# Pogramador_FT230XQ.net
KiCad netlist of a schematic drawn in EAGLE
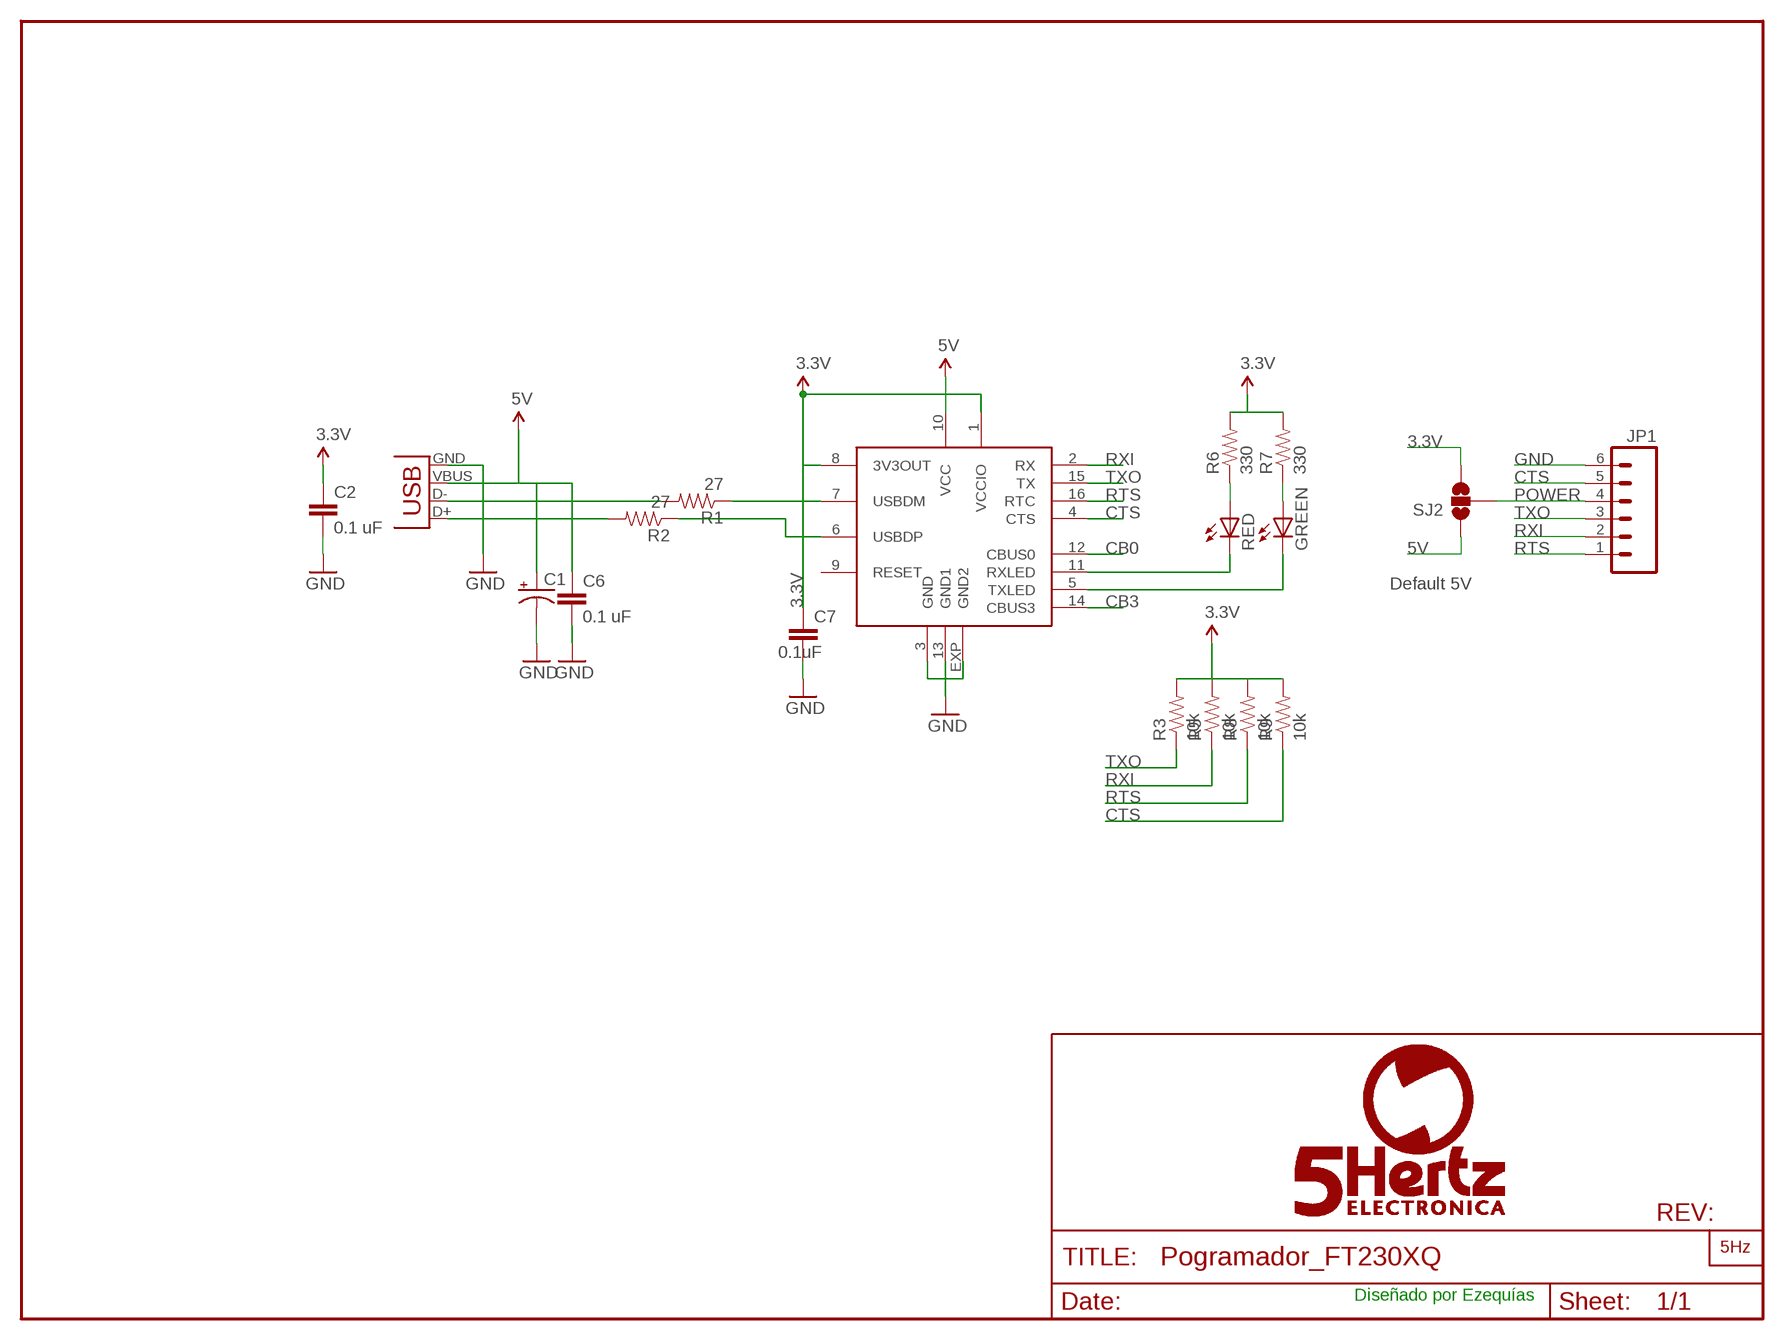
[diagram p0: schematic, sheet 1]

(export (version "E")
  (design (tool "Eeschema 10.0.6"))
  (components
    (comp (ref "C1")
      (value "CAP_POL1206")
      (footprint "eagle-import:EIA3216")
      (libsource (lib "eagle-import") (part "CAP_POL1206"))
    )
    (comp (ref "C2")
      (value "0.1 uF")
      (footprint "eagle-import:0603-CAP")
      (libsource (lib "eagle-import") (part "CAP0603-CAP"))
    )
    (comp (ref "C6")
      (value "0.1 uF")
      (footprint "eagle-import:0603-CAP")
      (libsource (lib "eagle-import") (part "CAP0603-CAP"))
    )
    (comp (ref "C7")
      (value "0.1uF")
      (footprint "eagle-import:0603-CAP")
      (libsource (lib "eagle-import") (part "CAP0603-CAP"))
    )
    (comp (ref "GREEN")
      (value "LED0603")
      (footprint "eagle-import:LED-0603")
      (libsource (lib "eagle-import") (part "LED0603"))
    )
    (comp (ref "JP1")
      (value "M06SIP")
      (footprint "eagle-import:1X06")
      (libsource (lib "eagle-import") (part "M06SIP"))
    )
    (comp (ref "R1")
      (value "27")
      (footprint "eagle-import:0603-RES")
      (libsource (lib "eagle-import") (part "RESISTOR0603-RES"))
    )
    (comp (ref "R2")
      (value "27")
      (footprint "eagle-import:0603-RES")
      (libsource (lib "eagle-import") (part "RESISTOR0603-RES"))
    )
    (comp (ref "R3")
      (value "10k")
      (footprint "eagle-import:0603-RES")
      (libsource (lib "eagle-import") (part "RESISTOR0603-RES"))
    )
    (comp (ref "R5")
      (value "10k")
      (footprint "eagle-import:0603-RES")
      (libsource (lib "eagle-import") (part "RESISTOR0603-RES"))
    )
    (comp (ref "R6")
      (value "330")
      (footprint "eagle-import:0603-RES")
      (libsource (lib "eagle-import") (part "RESISTOR0603-RES"))
    )
    (comp (ref "R7")
      (value "330")
      (footprint "eagle-import:0603-RES")
      (libsource (lib "eagle-import") (part "RESISTOR0603-RES"))
    )
    (comp (ref "R8")
      (value "10k")
      (footprint "eagle-import:0603-RES")
      (libsource (lib "eagle-import") (part "RESISTOR0603-RES"))
    )
    (comp (ref "R9")
      (value "10k")
      (footprint "eagle-import:0603-RES")
      (libsource (lib "eagle-import") (part "RESISTOR0603-RES"))
    )
    (comp (ref "RED")
      (value "LED0603")
      (footprint "eagle-import:LED-0603")
      (libsource (lib "eagle-import") (part "LED0603"))
    )
    (comp (ref "SJ2")
      (value "SOLDERJUMPER_2WAYS")
      (footprint "eagle-import:SJ_3")
      (libsource (lib "eagle-import") (part "SOLDERJUMPER_2WAYS"))
    )
    (comp (ref "U$2")
      (value "LOGO2_SILKL5MM")
      (footprint "eagle-import:LARGO2_5MM")
      (libsource (lib "eagle-import") (part "LOGO2_SILKL5MM"))
    )
    (comp (ref "U$5")
      (value "FT230")
      (footprint "eagle-import:QFN-16")
      (libsource (lib "eagle-import") (part "FT230"))
    )
    (comp (ref "X1")
      (value "USBSMD")
      (footprint "eagle-import:USB-MINIB")
      (libsource (lib "eagle-import") (part "USBSMD"))
    )
  )
  (nets
    (net (code "1") (name "/CB0") (class "Default")
      (node (ref "U$5") (pin "12") (pinfunction "CBUS0_12") (pintype "bidirectional"))
    )
    (net (code "2") (name "/CB3") (class "Default")
      (node (ref "U$5") (pin "14") (pinfunction "CBUS3_14") (pintype "bidirectional"))
    )
    (net (code "3") (name "/CTS") (class "Default")
      (node (ref "JP1") (pin "5") (pinfunction "5_5") (pintype "passive"))
      (node (ref "R9") (pin "1") (pinfunction "1_1") (pintype "passive"))
      (node (ref "U$5") (pin "4") (pinfunction "CTS_4") (pintype "bidirectional"))
    )
    (net (code "4") (name "/POWER") (class "Default")
      (node (ref "JP1") (pin "4") (pinfunction "4_4") (pintype "passive"))
      (node (ref "SJ2") (pin "2") (pinfunction "2_2") (pintype "passive"))
    )
    (net (code "5") (name "/RTS") (class "Default")
      (node (ref "JP1") (pin "1") (pinfunction "1_1") (pintype "passive"))
      (node (ref "R8") (pin "1") (pinfunction "1_1") (pintype "passive"))
      (node (ref "U$5") (pin "16") (pinfunction "RTC_16") (pintype "bidirectional"))
    )
    (net (code "6") (name "/RXI") (class "Default")
      (node (ref "JP1") (pin "2") (pinfunction "2_2") (pintype "passive"))
      (node (ref "R5") (pin "1") (pinfunction "1_1") (pintype "passive"))
      (node (ref "U$5") (pin "2") (pinfunction "RX_2") (pintype "bidirectional"))
    )
    (net (code "7") (name "/TXO") (class "Default")
      (node (ref "JP1") (pin "3") (pinfunction "3_3") (pintype "passive"))
      (node (ref "R3") (pin "1") (pinfunction "1_1") (pintype "passive"))
      (node (ref "U$5") (pin "15") (pinfunction "TX_15") (pintype "bidirectional"))
    )
    (net (code "8") (name "3.3V") (class "Default")
      (node (ref "C2") (pin "1") (pinfunction "1_1") (pintype "passive"))
      (node (ref "C7") (pin "1") (pinfunction "1_1") (pintype "passive"))
      (node (ref "R3") (pin "2") (pinfunction "2_2") (pintype "passive"))
      (node (ref "R5") (pin "2") (pinfunction "2_2") (pintype "passive"))
      (node (ref "R6") (pin "2") (pinfunction "2_2") (pintype "passive"))
      (node (ref "R7") (pin "2") (pinfunction "2_2") (pintype "passive"))
      (node (ref "R8") (pin "2") (pinfunction "2_2") (pintype "passive"))
      (node (ref "R9") (pin "2") (pinfunction "2_2") (pintype "passive"))
      (node (ref "SJ2") (pin "3") (pinfunction "3_3") (pintype "passive"))
      (node (ref "U$5") (pin "1") (pinfunction "VCCIO_1") (pintype "bidirectional"))
      (node (ref "U$5") (pin "8") (pinfunction "3V3OUT_8") (pintype "bidirectional"))
    )
    (net (code "9") (name "5V") (class "Default")
      (node (ref "C1") (pin "A") (pinfunction "+_A") (pintype "passive"))
      (node (ref "C6") (pin "1") (pinfunction "1_1") (pintype "passive"))
      (node (ref "SJ2") (pin "1") (pinfunction "1_1") (pintype "passive"))
      (node (ref "U$5") (pin "10") (pinfunction "VCC_10") (pintype "bidirectional"))
      (node (ref "X1") (pin "VBUS") (pinfunction "VBUS_VBUS") (pintype "bidirectional"))
    )
    (net (code "10") (name "GND") (class "Default")
      (node (ref "C1") (pin "C") (pinfunction "-_C") (pintype "passive"))
      (node (ref "C2") (pin "2") (pinfunction "2_2") (pintype "passive"))
      (node (ref "C6") (pin "2") (pinfunction "2_2") (pintype "passive"))
      (node (ref "C7") (pin "2") (pinfunction "2_2") (pintype "passive"))
      (node (ref "JP1") (pin "6") (pinfunction "6_6") (pintype "passive"))
      (node (ref "U$5") (pin "13") (pinfunction "GND1_13") (pintype "bidirectional"))
      (node (ref "U$5") (pin "3") (pinfunction "GND_3") (pintype "bidirectional"))
      (node (ref "U$5") (pin "EXP") (pinfunction "GND2_EXP") (pintype "bidirectional"))
      (node (ref "X1") (pin "GND") (pinfunction "GND_GND") (pintype "bidirectional"))
    )
    (net (code "11") (name "Net-(GREEN-PadA)") (class "Default")
      (node (ref "GREEN") (pin "A") (pinfunction "A_A") (pintype "passive"))
      (node (ref "R7") (pin "1") (pinfunction "1_1") (pintype "passive"))
    )
    (net (code "12") (name "Net-(R1-Pad2)") (class "Default")
      (node (ref "R1") (pin "2") (pinfunction "2_2") (pintype "passive"))
      (node (ref "X1") (pin "D-") (pinfunction "D-_D-") (pintype "bidirectional"))
    )
    (net (code "13") (name "Net-(R2-Pad2)") (class "Default")
      (node (ref "R2") (pin "2") (pinfunction "2_2") (pintype "passive"))
      (node (ref "X1") (pin "D+") (pinfunction "D+_D+") (pintype "bidirectional"))
    )
    (net (code "14") (name "Net-(R6-Pad1)") (class "Default")
      (node (ref "R6") (pin "1") (pinfunction "1_1") (pintype "passive"))
      (node (ref "RED") (pin "A") (pinfunction "A_A") (pintype "passive"))
    )
    (net (code "15") (name "Net-(U$5-RXLED)") (class "Default")
      (node (ref "RED") (pin "C") (pinfunction "C_C") (pintype "passive"))
      (node (ref "U$5") (pin "11") (pinfunction "RXLED_11") (pintype "bidirectional"))
    )
    (net (code "16") (name "Net-(U$5-TXLED)") (class "Default")
      (node (ref "GREEN") (pin "C") (pinfunction "C_C") (pintype "passive"))
      (node (ref "U$5") (pin "5") (pinfunction "TXLED_5") (pintype "bidirectional"))
    )
    (net (code "17") (name "Net-(U$5-USBDM)") (class "Default")
      (node (ref "R1") (pin "1") (pinfunction "1_1") (pintype "passive"))
      (node (ref "U$5") (pin "7") (pinfunction "USBDM_7") (pintype "bidirectional"))
    )
    (net (code "18") (name "Net-(U$5-USBDP)") (class "Default")
      (node (ref "R2") (pin "1") (pinfunction "1_1") (pintype "passive"))
      (node (ref "U$5") (pin "6") (pinfunction "USBDP_6") (pintype "bidirectional"))
    )
    (net (code "19") (name "unconnected-(U$5-RESET-Pad9)") (class "Default")
      (node (ref "U$5") (pin "9") (pinfunction "RESET_9") (pintype "bidirectional"))
    )
  )
)
